# ProPrj_ESP32C3CameraTrigger_2026-09-02_2.net
KiCad netlist of a schematic drawn in EasyEDA Pro
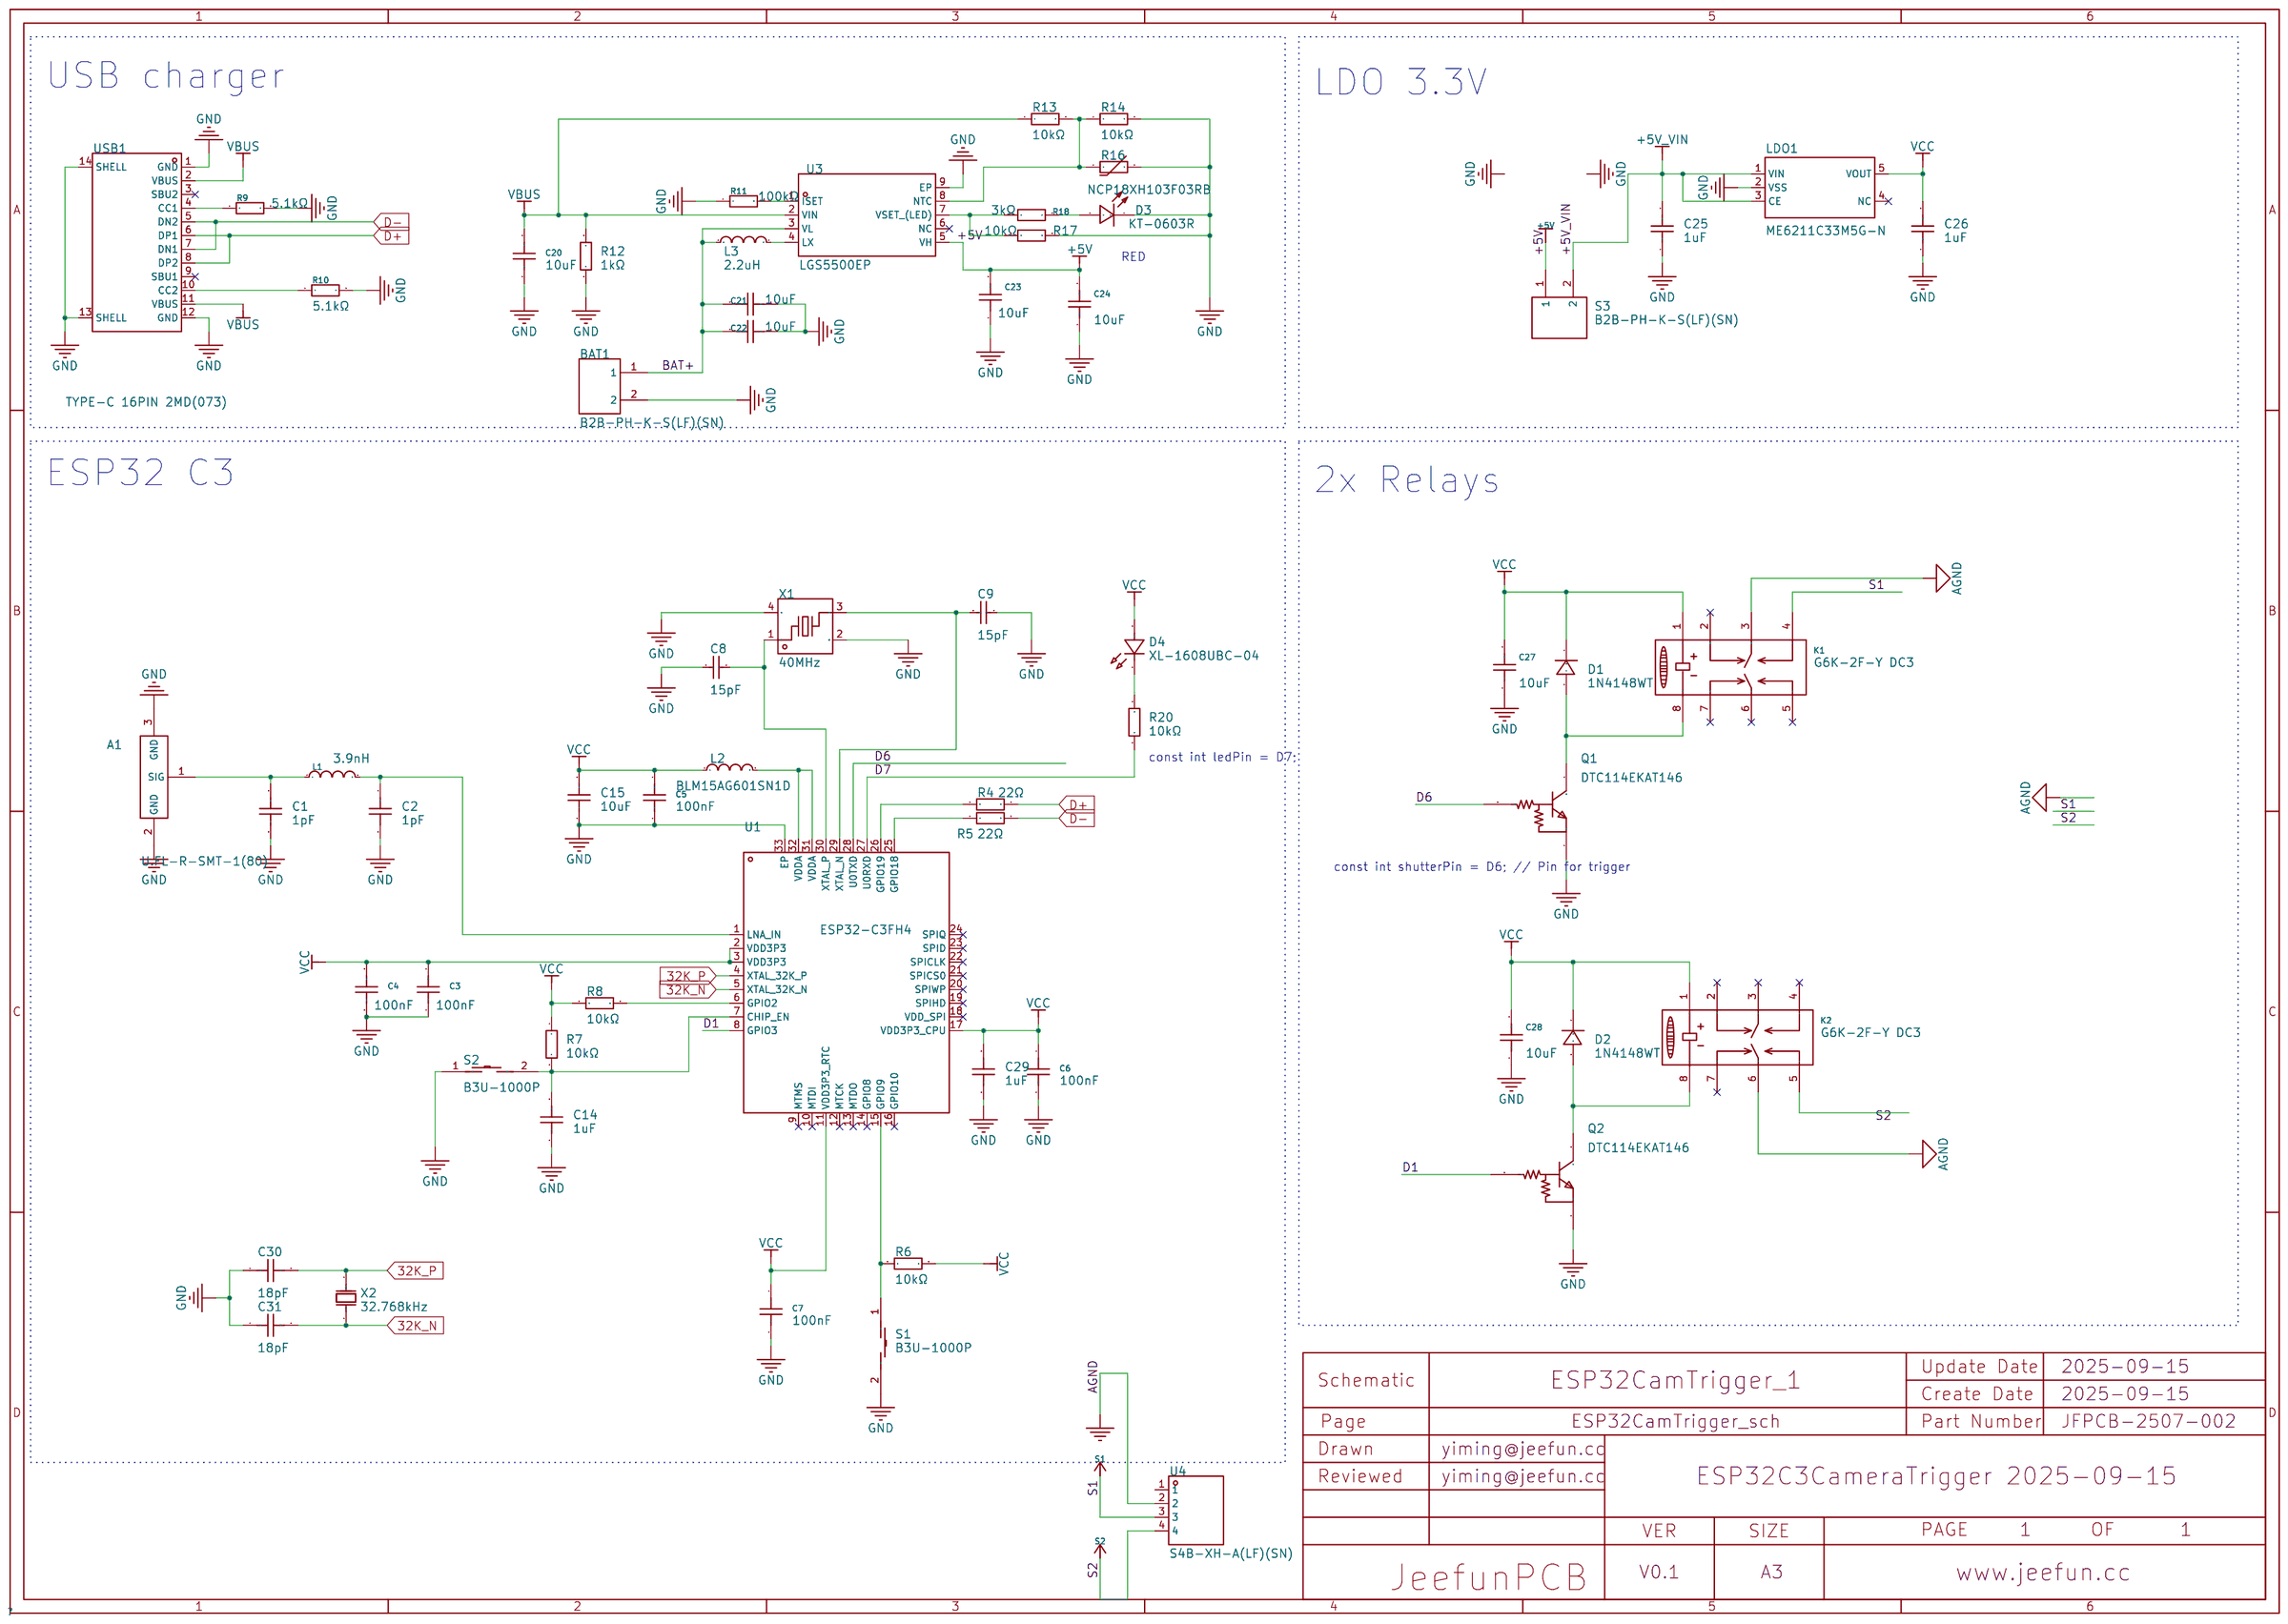
[diagram p0: schematic sheet]

(export (version "E")
  (design (tool "Eeschema 10.0.6"))
  (components
    (comp (ref "A1")
      (value "U.FL-R-SMT-1(80)")
      (footprint "easyedapro:RF-SMD_FRF05002-JSS103M")
      (fields (field (name "Manufacturer") "HRS(广濑)"))
      (libsource (lib "easyedapro") (part "U.FL-R-SMT-1(80)"))
    )
    (comp (ref "BAT1")
      (value "B2B-PH-K-S(LF)(SN)")
      (footprint "easyedapro:CONN-TH_B2B-PH-K-S")
      (fields (field (name "Manufacturer") "JST"))
      (libsource (lib "easyedapro") (part "B2B-PH-K-S(LF)(SN)"))
    )
    (comp (ref "C1")
      (value "1pF")
      (footprint "easyedapro:C0402")
      (fields
        (field (name "Manufacturer Part") "CC0402CRNPO9BN1R0")
        (field (name "Manufacturer") "YAGEO(国巨)")
      )
      (libsource (lib "easyedapro") (part "GCM1555C1H1R0BA16D"))
    )
    (comp (ref "C2")
      (value "1pF")
      (footprint "easyedapro:C0402")
      (fields
        (field (name "Manufacturer Part") "CC0402CRNPO9BN1R0")
        (field (name "Manufacturer") "YAGEO(国巨)")
      )
      (libsource (lib "easyedapro") (part "GCM1555C1H1R0BA16D"))
    )
    (comp (ref "C3")
      (value "100nF")
      (footprint "easyedapro:C0402")
      (fields
        (field (name "Manufacturer Part") "GRM155R71H104KE14D")
        (field (name "Manufacturer") "muRata(村田)")
      )
      (libsource (lib "easyedapro") (part "GRM155R71H104KE14D"))
    )
    (comp (ref "C4")
      (value "100nF")
      (footprint "easyedapro:C0402")
      (fields
        (field (name "Manufacturer Part") "GRM155R71H104KE14D")
        (field (name "Manufacturer") "muRata(村田)")
      )
      (libsource (lib "easyedapro") (part "GRM155R71H104KE14D"))
    )
    (comp (ref "C5")
      (value "100nF")
      (footprint "easyedapro:C0402")
      (fields
        (field (name "Manufacturer Part") "GRM155R71H104KE14D")
        (field (name "Manufacturer") "muRata(村田)")
      )
      (libsource (lib "easyedapro") (part "GRM155R71H104KE14D"))
    )
    (comp (ref "C6")
      (value "100nF")
      (footprint "easyedapro:C0402")
      (fields
        (field (name "Manufacturer Part") "GRM155R71H104KE14D")
        (field (name "Manufacturer") "muRata(村田)")
      )
      (libsource (lib "easyedapro") (part "GRM155R71H104KE14D"))
    )
    (comp (ref "C7")
      (value "100nF")
      (footprint "easyedapro:C0402")
      (fields
        (field (name "Manufacturer Part") "GRM155R71H104KE14D")
        (field (name "Manufacturer") "muRata(村田)")
      )
      (libsource (lib "easyedapro") (part "GRM155R71H104KE14D"))
    )
    (comp (ref "C8")
      (value "15pF")
      (footprint "easyedapro:C0402")
      (fields
        (field (name "Manufacturer Part") "GJM1555C1H150FB01D")
        (field (name "Manufacturer") "muRata(村田)")
      )
      (libsource (lib "easyedapro") (part "GJM1555C1H150FB01D"))
    )
    (comp (ref "C9")
      (value "15pF")
      (footprint "easyedapro:C0402")
      (fields
        (field (name "Manufacturer Part") "GJM1555C1H150FB01D")
        (field (name "Manufacturer") "muRata(村田)")
      )
      (libsource (lib "easyedapro") (part "GJM1555C1H150FB01D"))
    )
    (comp (ref "C14")
      (value "1uF")
      (footprint "easyedapro:C0603")
      (fields
        (field (name "Manufacturer Part") "CGA0603X5R105K500JT")
        (field (name "Manufacturer") "HRE(芯声)")
      )
      (libsource (lib "easyedapro") (part "CGA0603X5R105K500JT"))
    )
    (comp (ref "C15")
      (value "10uF")
      (footprint "easyedapro:C0603")
      (description "Capacitance:10uF Tolerance:±20% Tolerance:±20% Voltage Rating:25V Temperature Coefficient:X5R")
      (fields
        (field (name "Manufacturer Part") "CL10A106MA8NRNC")
        (field (name "Manufacturer") "SAMSUNG(三星)")
      )
      (libsource (lib "easyedapro") (part "CGA0603X5R106K100JT"))
    )
    (comp (ref "C20")
      (value "10uF")
      (footprint "easyedapro:C0603")
      (fields
        (field (name "Manufacturer Part") "CL10A106MA8NRNC")
        (field (name "Manufacturer") "SAMSUNG(三星)")
      )
      (libsource (lib "easyedapro") (part "CL10A106MA8NRNC"))
    )
    (comp (ref "C21")
      (value "10uF")
      (footprint "easyedapro:C0603")
      (fields
        (field (name "Manufacturer Part") "CL10A106MA8NRNC")
        (field (name "Manufacturer") "SAMSUNG(三星)")
      )
      (libsource (lib "easyedapro") (part "CL10A106MA8NRNC"))
    )
    (comp (ref "C22")
      (value "10uF")
      (footprint "easyedapro:C0603")
      (fields
        (field (name "Manufacturer Part") "CL10A106MA8NRNC")
        (field (name "Manufacturer") "SAMSUNG(三星)")
      )
      (libsource (lib "easyedapro") (part "CL10A106MA8NRNC"))
    )
    (comp (ref "C23")
      (value "10uF")
      (footprint "easyedapro:C0603")
      (fields
        (field (name "Manufacturer Part") "CL10A106MA8NRNC")
        (field (name "Manufacturer") "SAMSUNG(三星)")
      )
      (libsource (lib "easyedapro") (part "CL10A106MA8NRNC"))
    )
    (comp (ref "C24")
      (value "10uF")
      (footprint "easyedapro:C0603")
      (fields
        (field (name "Manufacturer Part") "CL10A106MA8NRNC")
        (field (name "Manufacturer") "SAMSUNG(三星)")
      )
      (libsource (lib "easyedapro") (part "CL10A106MA8NRNC"))
    )
    (comp (ref "C25")
      (value "1uF")
      (footprint "easyedapro:C0603")
      (fields
        (field (name "Manufacturer Part") "CGA0603X5R105K500JT")
        (field (name "Manufacturer") "HRE(芯声)")
      )
      (libsource (lib "easyedapro") (part "CGA0603X5R105K500JT"))
    )
    (comp (ref "C26")
      (value "1uF")
      (footprint "easyedapro:C0603")
      (fields
        (field (name "Manufacturer Part") "CGA0603X5R105K500JT")
        (field (name "Manufacturer") "HRE(芯声)")
      )
      (libsource (lib "easyedapro") (part "CGA0603X5R105K500JT"))
    )
    (comp (ref "C27")
      (value "10uF")
      (footprint "easyedapro:C0603")
      (fields
        (field (name "Manufacturer Part") "CL10A106MA8NRNC")
        (field (name "Manufacturer") "SAMSUNG(三星)")
      )
      (libsource (lib "easyedapro") (part "CL10A106MA8NRNC"))
    )
    (comp (ref "C28")
      (value "10uF")
      (footprint "easyedapro:C0603")
      (fields
        (field (name "Manufacturer Part") "CL10A106MA8NRNC")
        (field (name "Manufacturer") "SAMSUNG(三星)")
      )
      (libsource (lib "easyedapro") (part "CL10A106MA8NRNC"))
    )
    (comp (ref "C29")
      (value "1uF")
      (footprint "easyedapro:C0603")
      (fields
        (field (name "Manufacturer Part") "CGA0603X5R105K500JT")
        (field (name "Manufacturer") "HRE(芯声)")
      )
      (libsource (lib "easyedapro") (part "CGA0603X5R105K500JT"))
    )
    (comp (ref "C30")
      (value "18pF")
      (footprint "easyedapro:C0402")
      (fields
        (field (name "Manufacturer Part") "GRM1555C1H180FA01D")
        (field (name "Manufacturer") "muRata(村田)")
      )
      (libsource (lib "easyedapro") (part "GRM1555C1H180FA01D"))
    )
    (comp (ref "C31")
      (value "18pF")
      (footprint "easyedapro:C0402")
      (fields
        (field (name "Manufacturer Part") "GRM1555C1H180FA01D")
        (field (name "Manufacturer") "muRata(村田)")
      )
      (libsource (lib "easyedapro") (part "GRM1555C1H180FA01D"))
    )
    (comp (ref "D1")
      (value "1N4148WT")
      (footprint "easyedapro:SOD-523_L1.2-W0.8-LS1.6-RD")
      (fields (field (name "Manufacturer") "onsemi(安森美)"))
      (libsource (lib "easyedapro") (part "1N4148WT_C232841"))
    )
    (comp (ref "D2")
      (value "1N4148WT")
      (footprint "easyedapro:SOD-523_L1.2-W0.8-LS1.6-RD")
      (fields (field (name "Manufacturer") "onsemi(安森美)"))
      (libsource (lib "easyedapro") (part "1N4148WT_C232841"))
    )
    (comp (ref "D3")
      (value "KT-0603R")
      (footprint "easyedapro:LED0603-RD")
      (fields (field (name "Manufacturer") "KENTO"))
      (libsource (lib "easyedapro") (part "KT-0603R"))
    )
    (comp (ref "D4")
      (value "XL-1608UBC-04")
      (footprint "easyedapro:LED0603-RD_BLUE")
      (fields (field (name "Manufacturer") "XINGLIGHT(成兴光)"))
      (libsource (lib "easyedapro") (part "XL-1608UBC-04"))
    )
    (comp (ref "K1")
      (value "G6K-2F-Y DC3")
      (footprint "easyedapro:RELAY-SMD_G6K-2F-Y")
      (fields (field (name "Manufacturer") "OMRON(欧姆龙)"))
      (libsource (lib "easyedapro") (part "G6K-2F-Y3VDC"))
    )
    (comp (ref "K2")
      (value "G6K-2F-Y DC3")
      (footprint "easyedapro:RELAY-SMD_G6K-2F-Y")
      (fields (field (name "Manufacturer") "OMRON(欧姆龙)"))
      (libsource (lib "easyedapro") (part "G6K-2F-Y3VDC"))
    )
    (comp (ref "L1")
      (value "3.9nH")
      (footprint "easyedapro:L0402")
      (fields (field (name "Manufacturer Part") "LQG15HS3N9S02D") (field (name "Manufacturer") "muRata(村田)"))
      (libsource (lib "easyedapro") (part "LQG15HS3N9S02D"))
    )
    (comp (ref "L2")
      (value "BLM15AG601SN1D")
      (footprint "easyedapro:L0603")
      (fields (field (name "Manufacturer") "muRata(村田)"))
      (libsource (lib "easyedapro") (part "ACMS160808A3012A"))
    )
    (comp (ref "L3")
      (value "2.2uH")
      (footprint "easyedapro:IND-SMD_L7.1-W6.5-P5.60")
      (fields (field (name "Manufacturer Part") "SPM6530T-2R2M") (field (name "Manufacturer") "TDK"))
      (libsource (lib "easyedapro") (part "SPM6530T-2R2M"))
    )
    (comp (ref "LDO1")
      (value "ME6211C33M5G-N")
      (footprint "easyedapro:SOT-23-5_L3.0-W1.7-P0.95-LS2.8-BL")
      (fields (field (name "Manufacturer") "MICRONE(南京微盟)"))
      (libsource (lib "easyedapro") (part "ME6211C33M5G-N"))
    )
    (comp (ref "Q1")
      (value "DTC114EKAT146")
      (footprint "easyedapro:SOT-346_L2.9-W1.6-P1.90-LS2.8-TR-CW")
      (fields (field (name "Manufacturer") "ROHM(罗姆)"))
      (libsource (lib "easyedapro") (part "DTC114EKAT146"))
    )
    (comp (ref "Q2")
      (value "DTC114EKAT146")
      (footprint "easyedapro:SOT-346_L2.9-W1.6-P1.90-LS2.8-TR-CW")
      (fields (field (name "Manufacturer") "ROHM(罗姆)"))
      (libsource (lib "easyedapro") (part "DTC114EKAT146"))
    )
    (comp (ref "R4")
      (value "22Ω")
      (footprint "easyedapro:R0402")
      (fields (field (name "Manufacturer Part") "RC0402JR-0722RL") (field (name "Manufacturer") "YAGEO(国巨)"))
      (libsource (lib "easyedapro") (part "RC0402JR-0722RL"))
    )
    (comp (ref "R5")
      (value "22Ω")
      (footprint "easyedapro:R0402")
      (fields (field (name "Manufacturer Part") "RC0402JR-0722RL") (field (name "Manufacturer") "YAGEO(国巨)"))
      (libsource (lib "easyedapro") (part "RC0402JR-0722RL"))
    )
    (comp (ref "R6")
      (value "10kΩ")
      (footprint "easyedapro:R0402")
      (fields (field (name "Manufacturer Part") "RC0402FR-0710KL") (field (name "Manufacturer") "YAGEO(国巨)"))
      (libsource (lib "easyedapro") (part "RC0402FR-0710KL"))
    )
    (comp (ref "R7")
      (value "10kΩ")
      (footprint "easyedapro:R0402")
      (fields (field (name "Manufacturer Part") "RC0402FR-0710KL") (field (name "Manufacturer") "YAGEO(国巨)"))
      (libsource (lib "easyedapro") (part "RC0402FR-0710KL"))
    )
    (comp (ref "R8")
      (value "10kΩ")
      (footprint "easyedapro:R0402")
      (fields (field (name "Manufacturer Part") "RC0402FR-0710KL") (field (name "Manufacturer") "YAGEO(国巨)"))
      (libsource (lib "easyedapro") (part "RC0402FR-0710KL"))
    )
    (comp (ref "R9")
      (value "5.1kΩ")
      (footprint "easyedapro:R0402")
      (fields
        (field (name "Manufacturer Part") "0402WGF5101TCE")
        (field (name "Manufacturer") "UNI-ROYAL(厚声)")
      )
      (libsource (lib "easyedapro") (part "0402WGF5101TCE"))
    )
    (comp (ref "R10")
      (value "5.1kΩ")
      (footprint "easyedapro:R0402")
      (fields
        (field (name "Manufacturer Part") "0402WGF5101TCE")
        (field (name "Manufacturer") "UNI-ROYAL(厚声)")
      )
      (libsource (lib "easyedapro") (part "0402WGF5101TCE"))
    )
    (comp (ref "R11")
      (value "100kΩ")
      (footprint "easyedapro:R0402")
      (fields
        (field (name "Manufacturer Part") "0402WGF1003TCE")
        (field (name "Manufacturer") "UNI-ROYAL(厚声)")
      )
      (libsource (lib "easyedapro") (part "0402WGF1003TCE"))
    )
    (comp (ref "R12")
      (value "1kΩ")
      (footprint "easyedapro:R0603")
      (fields
        (field (name "Manufacturer Part") "0603WAJ0102T5E")
        (field (name "Manufacturer") "UNI-ROYAL(厚声)")
      )
      (libsource (lib "easyedapro") (part "0603WAJ0102T5E"))
    )
    (comp (ref "R13")
      (value "10kΩ")
      (footprint "easyedapro:R0402")
      (fields (field (name "Manufacturer Part") "RC0402FR-0710KL") (field (name "Manufacturer") "YAGEO(国巨)"))
      (libsource (lib "easyedapro") (part "RC0402FR-0710KL"))
    )
    (comp (ref "R14")
      (value "10kΩ")
      (footprint "easyedapro:R0402")
      (fields (field (name "Manufacturer Part") "RC0402FR-0710KL") (field (name "Manufacturer") "YAGEO(国巨)"))
      (libsource (lib "easyedapro") (part "RC0402FR-0710KL"))
    )
    (comp (ref "R16")
      (value "NCP18XH103F03RB")
      (footprint "easyedapro:R0603")
      (fields (field (name "Manufacturer") "muRata(村田)"))
      (libsource (lib "easyedapro") (part "NCP18XH103F03RB"))
    )
    (comp (ref "R17")
      (value "10kΩ")
      (footprint "easyedapro:R0402")
      (fields (field (name "Manufacturer Part") "RC0402FR-0710KL") (field (name "Manufacturer") "YAGEO(国巨)"))
      (libsource (lib "easyedapro") (part "RC0402FR-0710KL"))
    )
    (comp (ref "R18")
      (value "3kΩ")
      (footprint "easyedapro:R0603")
      (fields
        (field (name "Manufacturer Part") "0402WGF3001TCE")
        (field (name "Manufacturer") "UNI-ROYAL(厚声)")
      )
      (libsource (lib "easyedapro") (part "0603WAF3001T5E"))
    )
    (comp (ref "R20")
      (value "10kΩ")
      (footprint "easyedapro:R0402")
      (fields (field (name "Manufacturer Part") "RC0402FR-0710KL") (field (name "Manufacturer") "YAGEO(国巨)"))
      (libsource (lib "easyedapro") (part "RC0402FR-0710KL"))
    )
    (comp (ref "S1")
      (value "B3U-1000P")
      (footprint "easyedapro:KEY-SMD_B3U-1000PM")
      (fields (field (name "Manufacturer") "OMRON(欧姆龙)"))
      (libsource (lib "easyedapro") (part "B3U-1000P"))
    )
    (comp (ref "S2")
      (value "B3U-1000P")
      (footprint "easyedapro:KEY-SMD_B3U-1000PM")
      (fields (field (name "Manufacturer") "OMRON(欧姆龙)"))
      (libsource (lib "easyedapro") (part "B3U-1000P"))
    )
    (comp (ref "S3")
      (value "B2B-PH-K-S(LF)(SN)")
      (footprint "easyedapro:CONN-TH_B2B-PH-K-S")
      (fields (field (name "Manufacturer") "JST"))
      (libsource (lib "easyedapro") (part "B2B-PH-K-S(LF)(SN)"))
    )
    (comp (ref "U1")
      (value "ESP32-C3FH4")
      (footprint "easyedapro:QFN-32_L5.0-W5.0-P0.50-TL-EP3.7")
      (fields (field (name "Manufacturer") "ESPRESSIF(乐鑫)"))
      (libsource (lib "easyedapro") (part "ESP32-C3"))
    )
    (comp (ref "U3")
      (value "LGS5500EP")
      (footprint "easyedapro:ESOP-8_L4.9-W3.9-P1.27-LS6.0-TL-EP3.3")
      (fields (field (name "Manufacturer") "Legend-Si(棱晶半导体)"))
      (libsource (lib "easyedapro") (part "LGS5500EP"))
    )
    (comp (ref "U4")
      (value "S4B-XH-A(LF)(SN)")
      (footprint "easyedapro:CONN-TH_S4B-XH-A-LF-SN")
      (fields (field (name "Manufacturer") "JST"))
      (libsource (lib "easyedapro") (part "S4B-XH-A (LF)(SN)"))
    )
    (comp (ref "USB1")
      (value "TYPE-C 16PIN 2MD(073)")
      (footprint "easyedapro:USB-C-SMD_TYPE-C-6PIN-2MD-073")
      (fields (field (name "Manufacturer") "SHOU HAN(首韩)"))
      (libsource (lib "easyedapro") (part "TYPE-C 16PIN 2MD(073)"))
    )
    (comp (ref "X1")
      (value "40MHz")
      (footprint "easyedapro:CRYSTAL-SMD_4P-L2.0-W1.6-BL-2")
      (fields (field (name "Manufacturer Part") "T201640MFBDE2X") (field (name "Manufacturer") "YJX(雅晶鑫)"))
      (libsource (lib "easyedapro") (part "T201640MFBDE2X"))
    )
    (comp (ref "X2")
      (value "32.768kHz")
      (footprint "easyedapro:CRYSTAL-SMD_L3.2-W1.5-1")
      (fields
        (field (name "Manufacturer Part") "XKXGI-SUA-32.768K")
        (field (name "Manufacturer") "YXC(扬兴晶振)")
      )
      (libsource (lib "easyedapro") (part "XKXGI-SUA-32.768K"))
    )
  )
  (nets
    (net (code "1") (name "+5V") (class "Default")
      (node (ref "C23") (pin "2") (pinfunction "2_2") (pintype "input"))
      (node (ref "C24") (pin "2") (pinfunction "2_2") (pintype "input"))
      (node (ref "S3") (pin "1") (pinfunction "1_1") (pintype "input"))
      (node (ref "U3") (pin "5") (pinfunction "VH_5") (pintype "unspecified"))
    )
    (net (code "2") (name "+5V_VIN") (class "Default")
      (node (ref "C25") (pin "2") (pinfunction "2_2") (pintype "unspecified"))
      (node (ref "LDO1") (pin "1") (pinfunction "VIN_1") (pintype "unspecified"))
      (node (ref "LDO1") (pin "3") (pinfunction "CE_3") (pintype "unspecified"))
      (node (ref "S3") (pin "2") (pinfunction "2_2") (pintype "input"))
    )
    (net (code "3") (name "/BAT+") (class "Default")
      (node (ref "BAT1") (pin "1") (pinfunction "1_1") (pintype "input"))
      (node (ref "C21") (pin "2") (pinfunction "2_2") (pintype "input"))
      (node (ref "C22") (pin "2") (pinfunction "2_2") (pintype "input"))
      (node (ref "L3") (pin "1") (pinfunction "1_1") (pintype "unspecified"))
      (node (ref "U3") (pin "3") (pinfunction "VL_3") (pintype "unspecified"))
    )
    (net (code "4") (name "/D1") (class "Default")
      (node (ref "Q2") (pin "2") (pinfunction "B_2") (pintype "unspecified"))
      (node (ref "U1") (pin "8") (pinfunction "GPIO3_8") (pintype "unspecified"))
    )
    (net (code "5") (name "/D6") (class "Default")
      (node (ref "Q1") (pin "2") (pinfunction "B_2") (pintype "unspecified"))
      (node (ref "U1") (pin "28") (pinfunction "U0TXD_28") (pintype "unspecified"))
    )
    (net (code "6") (name "/D7") (class "Default")
      (node (ref "R20") (pin "1") (pinfunction "1_1") (pintype "input"))
      (node (ref "U1") (pin "27") (pinfunction "U0RXD_27") (pintype "unspecified"))
    )
    (net (code "7") (name "32K_N") (class "Default")
      (node (ref "C31") (pin "2") (pinfunction "2_2") (pintype "unspecified"))
      (node (ref "U1") (pin "5") (pinfunction "XTAL_32K_N_5") (pintype "unspecified"))
      (node (ref "X2") (pin "1") (pinfunction "OSC1_1") (pintype "input"))
    )
    (net (code "8") (name "32K_P") (class "Default")
      (node (ref "C30") (pin "2") (pinfunction "2_2") (pintype "unspecified"))
      (node (ref "U1") (pin "4") (pinfunction "XTAL_32K_P_4") (pintype "unspecified"))
      (node (ref "X2") (pin "2") (pinfunction "OSC2_2") (pintype "input"))
    )
    (net (code "9") (name "AGND") (class "Default")
      (node (ref "K1") (pin "3") (pinfunction "3_3") (pintype "input"))
      (node (ref "K2") (pin "6") (pinfunction "6_6") (pintype "input"))
      (node (ref "U4") (pin "2") (pinfunction "2_2") (pintype "unspecified"))
    )
    (net (code "10") (name "D+") (class "Default")
      (node (ref "R4") (pin "2") (pinfunction "2_2") (pintype "input"))
      (node (ref "USB1") (pin "6") (pinfunction "DP1_6") (pintype "unspecified"))
      (node (ref "USB1") (pin "8") (pinfunction "DP2_8") (pintype "unspecified"))
    )
    (net (code "11") (name "D-") (class "Default")
      (node (ref "R5") (pin "2") (pinfunction "2_2") (pintype "input"))
      (node (ref "USB1") (pin "5") (pinfunction "DN2_5") (pintype "unspecified"))
      (node (ref "USB1") (pin "7") (pinfunction "DN1_7") (pintype "unspecified"))
    )
    (net (code "12") (name "GND") (class "Default")
      (node (ref "A1") (pin "2") (pinfunction "GND_2") (pintype "unspecified"))
      (node (ref "A1") (pin "3") (pinfunction "GND_3") (pintype "unspecified"))
      (node (ref "BAT1") (pin "2") (pinfunction "2_2") (pintype "input"))
      (node (ref "C1") (pin "2") (pinfunction "2_2") (pintype "unspecified"))
      (node (ref "C14") (pin "1") (pinfunction "1_1") (pintype "unspecified"))
      (node (ref "C15") (pin "1") (pinfunction "1_1") (pintype "unspecified"))
      (node (ref "C2") (pin "2") (pinfunction "2_2") (pintype "unspecified"))
      (node (ref "C20") (pin "1") (pinfunction "1_1") (pintype "input"))
      (node (ref "C21") (pin "1") (pinfunction "1_1") (pintype "input"))
      (node (ref "C22") (pin "1") (pinfunction "1_1") (pintype "input"))
      (node (ref "C23") (pin "1") (pinfunction "1_1") (pintype "input"))
      (node (ref "C24") (pin "1") (pinfunction "1_1") (pintype "input"))
      (node (ref "C25") (pin "1") (pinfunction "1_1") (pintype "unspecified"))
      (node (ref "C26") (pin "1") (pinfunction "1_1") (pintype "unspecified"))
      (node (ref "C27") (pin "1") (pinfunction "1_1") (pintype "input"))
      (node (ref "C28") (pin "1") (pinfunction "1_1") (pintype "input"))
      (node (ref "C29") (pin "1") (pinfunction "1_1") (pintype "unspecified"))
      (node (ref "C3") (pin "1") (pinfunction "1_1") (pintype "input"))
      (node (ref "C30") (pin "1") (pinfunction "1_1") (pintype "unspecified"))
      (node (ref "C31") (pin "1") (pinfunction "1_1") (pintype "unspecified"))
      (node (ref "C4") (pin "1") (pinfunction "1_1") (pintype "input"))
      (node (ref "C5") (pin "2") (pinfunction "2_2") (pintype "input"))
      (node (ref "C6") (pin "2") (pinfunction "2_2") (pintype "input"))
      (node (ref "C7") (pin "2") (pinfunction "2_2") (pintype "input"))
      (node (ref "C8") (pin "1") (pinfunction "1_1") (pintype "input"))
      (node (ref "C9") (pin "2") (pinfunction "2_2") (pintype "input"))
      (node (ref "D3") (pin "1") (pinfunction "K_1") (pintype "unspecified"))
      (node (ref "LDO1") (pin "2") (pinfunction "VSS_2") (pintype "unspecified"))
      (node (ref "Q1") (pin "1") (pinfunction "E_1") (pintype "unspecified"))
      (node (ref "Q2") (pin "1") (pinfunction "E_1") (pintype "unspecified"))
      (node (ref "R10") (pin "2") (pinfunction "2_2") (pintype "input"))
      (node (ref "R11") (pin "1") (pinfunction "1_1") (pintype "input"))
      (node (ref "R12") (pin "1") (pinfunction "1_1") (pintype "input"))
      (node (ref "R14") (pin "2") (pinfunction "2_2") (pintype "input"))
      (node (ref "R16") (pin "2") (pinfunction "2_2") (pintype "input"))
      (node (ref "R17") (pin "2") (pinfunction "2_2") (pintype "input"))
      (node (ref "R9") (pin "2") (pinfunction "2_2") (pintype "input"))
      (node (ref "S1") (pin "2") (pinfunction "2_2") (pintype "unspecified"))
      (node (ref "S2") (pin "1") (pinfunction "1_1") (pintype "unspecified"))
      (node (ref "U1") (pin "33") (pinfunction "EP_33") (pintype "unspecified"))
      (node (ref "U3") (pin "9") (pinfunction "EP_9") (pintype "unspecified"))
      (node (ref "USB1") (pin "1") (pinfunction "GND_1") (pintype "unspecified"))
      (node (ref "USB1") (pin "12") (pinfunction "GND_12") (pintype "unspecified"))
      (node (ref "USB1") (pin "13") (pinfunction "SHELL_13") (pintype "unspecified"))
      (node (ref "USB1") (pin "14") (pinfunction "SHELL_14") (pintype "unspecified"))
      (node (ref "X1") (pin "2") (pinfunction "GND_2") (pintype "input"))
      (node (ref "X1") (pin "4") (pinfunction "GND_4") (pintype "input"))
    )
    (net (code "13") (name "Net-(A1-SIG)") (class "Default")
      (node (ref "A1") (pin "1") (pinfunction "SIG_1") (pintype "unspecified"))
      (node (ref "C1") (pin "1") (pinfunction "1_1") (pintype "unspecified"))
      (node (ref "L1") (pin "1") (pinfunction "1_1") (pintype "input"))
    )
    (net (code "14") (name "Net-(D1-A)") (class "Default")
      (node (ref "D1") (pin "2") (pinfunction "A_2") (pintype "unspecified"))
      (node (ref "K1") (pin "8") (pinfunction "8_8") (pintype "input"))
      (node (ref "Q1") (pin "3") (pinfunction "C_3") (pintype "unspecified"))
    )
    (net (code "15") (name "Net-(D2-A)") (class "Default")
      (node (ref "D2") (pin "2") (pinfunction "A_2") (pintype "unspecified"))
      (node (ref "K2") (pin "8") (pinfunction "8_8") (pintype "input"))
      (node (ref "Q2") (pin "3") (pinfunction "C_3") (pintype "unspecified"))
    )
    (net (code "16") (name "Net-(D3-A)") (class "Default")
      (node (ref "D3") (pin "2") (pinfunction "A_2") (pintype "unspecified"))
      (node (ref "R18") (pin "2") (pinfunction "2_2") (pintype "input"))
    )
    (net (code "17") (name "Net-(D4-K)") (class "Default")
      (node (ref "D4") (pin "1") (pinfunction "K_1") (pintype "unspecified"))
      (node (ref "R20") (pin "2") (pinfunction "2_2") (pintype "input"))
    )
    (net (code "18") (name "Net-(L2-Pad2)") (class "Default")
      (node (ref "L2") (pin "2") (pinfunction "2_2") (pintype "unspecified"))
      (node (ref "U1") (pin "31") (pinfunction "VDDA_31") (pintype "unspecified"))
      (node (ref "U1") (pin "32") (pinfunction "VDDA_32") (pintype "unspecified"))
    )
    (net (code "19") (name "Net-(U1-CHIP_EN)") (class "Default")
      (node (ref "C14") (pin "2") (pinfunction "2_2") (pintype "unspecified"))
      (node (ref "R7") (pin "2") (pinfunction "2_2") (pintype "input"))
      (node (ref "S2") (pin "2") (pinfunction "2_2") (pintype "unspecified"))
      (node (ref "U1") (pin "7") (pinfunction "CHIP_EN_7") (pintype "unspecified"))
    )
    (net (code "20") (name "Net-(U1-GPIO2)") (class "Default")
      (node (ref "R8") (pin "2") (pinfunction "2_2") (pintype "input"))
      (node (ref "U1") (pin "6") (pinfunction "GPIO2_6") (pintype "unspecified"))
    )
    (net (code "21") (name "Net-(U1-GPIO9)") (class "Default")
      (node (ref "R6") (pin "1") (pinfunction "1_1") (pintype "input"))
      (node (ref "S1") (pin "1") (pinfunction "1_1") (pintype "unspecified"))
      (node (ref "U1") (pin "15") (pinfunction "GPIO9_15") (pintype "unspecified"))
    )
    (net (code "22") (name "Net-(U1-GPIO18)") (class "Default")
      (node (ref "R5") (pin "1") (pinfunction "1_1") (pintype "input"))
      (node (ref "U1") (pin "25") (pinfunction "GPIO18_25") (pintype "unspecified"))
    )
    (net (code "23") (name "Net-(U1-GPIO19)") (class "Default")
      (node (ref "R4") (pin "1") (pinfunction "1_1") (pintype "input"))
      (node (ref "U1") (pin "26") (pinfunction "GPIO19_26") (pintype "unspecified"))
    )
    (net (code "24") (name "Net-(U1-LNA_IN)") (class "Default")
      (node (ref "C2") (pin "1") (pinfunction "1_1") (pintype "unspecified"))
      (node (ref "L1") (pin "2") (pinfunction "2_2") (pintype "input"))
      (node (ref "U1") (pin "1") (pinfunction "LNA_IN_1") (pintype "unspecified"))
    )
    (net (code "25") (name "Net-(U1-XTAL_N)") (class "Default")
      (node (ref "C9") (pin "1") (pinfunction "1_1") (pintype "input"))
      (node (ref "U1") (pin "29") (pinfunction "XTAL_N_29") (pintype "unspecified"))
      (node (ref "X1") (pin "3") (pinfunction "3_3") (pintype "input"))
    )
    (net (code "26") (name "Net-(U1-XTAL_P)") (class "Default")
      (node (ref "C8") (pin "2") (pinfunction "2_2") (pintype "input"))
      (node (ref "U1") (pin "30") (pinfunction "XTAL_P_30") (pintype "unspecified"))
      (node (ref "X1") (pin "1") (pinfunction "1_1") (pintype "input"))
    )
    (net (code "27") (name "Net-(U3-ISET)") (class "Default")
      (node (ref "R11") (pin "2") (pinfunction "2_2") (pintype "input"))
      (node (ref "U3") (pin "1") (pinfunction "ISET_1") (pintype "unspecified"))
    )
    (net (code "28") (name "Net-(U3-LX)") (class "Default")
      (node (ref "L3") (pin "2") (pinfunction "2_2") (pintype "unspecified"))
      (node (ref "U3") (pin "4") (pinfunction "LX_4") (pintype "unspecified"))
    )
    (net (code "29") (name "Net-(U3-NTC)") (class "Default")
      (node (ref "R13") (pin "2") (pinfunction "2_2") (pintype "input"))
      (node (ref "R14") (pin "1") (pinfunction "1_1") (pintype "input"))
      (node (ref "R16") (pin "1") (pinfunction "1_1") (pintype "input"))
      (node (ref "U3") (pin "8") (pinfunction "NTC_8") (pintype "unspecified"))
    )
    (net (code "30") (name "Net-(U3-VSET_(LED))") (class "Default")
      (node (ref "R17") (pin "1") (pinfunction "1_1") (pintype "input"))
      (node (ref "R18") (pin "1") (pinfunction "1_1") (pintype "input"))
      (node (ref "U3") (pin "7") (pinfunction "VSET_(LED)_7") (pintype "unspecified"))
    )
    (net (code "31") (name "Net-(USB1-CC1)") (class "Default")
      (node (ref "R9") (pin "1") (pinfunction "1_1") (pintype "input"))
      (node (ref "USB1") (pin "4") (pinfunction "CC1_4") (pintype "unspecified"))
    )
    (net (code "32") (name "Net-(USB1-CC2)") (class "Default")
      (node (ref "R10") (pin "1") (pinfunction "1_1") (pintype "input"))
      (node (ref "USB1") (pin "10") (pinfunction "CC2_10") (pintype "unspecified"))
    )
    (net (code "33") (name "S1") (class "Default")
      (node (ref "K1") (pin "4") (pinfunction "4_4") (pintype "input"))
      (node (ref "U4") (pin "3") (pinfunction "3_3") (pintype "unspecified"))
    )
    (net (code "34") (name "S2") (class "Default")
      (node (ref "K2") (pin "5") (pinfunction "5_5") (pintype "input"))
      (node (ref "U4") (pin "4") (pinfunction "4_4") (pintype "unspecified"))
    )
    (net (code "35") (name "VBUS") (class "Default")
      (node (ref "C20") (pin "2") (pinfunction "2_2") (pintype "input"))
      (node (ref "R12") (pin "2") (pinfunction "2_2") (pintype "input"))
      (node (ref "R13") (pin "1") (pinfunction "1_1") (pintype "input"))
      (node (ref "U3") (pin "2") (pinfunction "VIN_2") (pintype "unspecified"))
      (node (ref "USB1") (pin "11") (pinfunction "VBUS_11") (pintype "unspecified"))
      (node (ref "USB1") (pin "2") (pinfunction "VBUS_2") (pintype "unspecified"))
    )
    (net (code "36") (name "VCC") (class "Default")
      (node (ref "C15") (pin "2") (pinfunction "2_2") (pintype "unspecified"))
      (node (ref "C26") (pin "2") (pinfunction "2_2") (pintype "unspecified"))
      (node (ref "C27") (pin "2") (pinfunction "2_2") (pintype "input"))
      (node (ref "C28") (pin "2") (pinfunction "2_2") (pintype "input"))
      (node (ref "C29") (pin "2") (pinfunction "2_2") (pintype "unspecified"))
      (node (ref "C3") (pin "2") (pinfunction "2_2") (pintype "input"))
      (node (ref "C4") (pin "2") (pinfunction "2_2") (pintype "input"))
      (node (ref "C5") (pin "1") (pinfunction "1_1") (pintype "input"))
      (node (ref "C6") (pin "1") (pinfunction "1_1") (pintype "input"))
      (node (ref "C7") (pin "1") (pinfunction "1_1") (pintype "input"))
      (node (ref "D1") (pin "1") (pinfunction "C_1") (pintype "unspecified"))
      (node (ref "D2") (pin "1") (pinfunction "C_1") (pintype "unspecified"))
      (node (ref "D4") (pin "2") (pinfunction "A_2") (pintype "unspecified"))
      (node (ref "K1") (pin "1") (pinfunction "1_1") (pintype "input"))
      (node (ref "K2") (pin "1") (pinfunction "1_1") (pintype "input"))
      (node (ref "L2") (pin "1") (pinfunction "1_1") (pintype "unspecified"))
      (node (ref "LDO1") (pin "5") (pinfunction "VOUT_5") (pintype "unspecified"))
      (node (ref "R6") (pin "2") (pinfunction "2_2") (pintype "input"))
      (node (ref "R7") (pin "1") (pinfunction "1_1") (pintype "input"))
      (node (ref "R8") (pin "1") (pinfunction "1_1") (pintype "input"))
      (node (ref "U1") (pin "11") (pinfunction "VDD3P3_RTC_11") (pintype "unspecified"))
      (node (ref "U1") (pin "17") (pinfunction "VDD3P3_CPU_17") (pintype "unspecified"))
      (node (ref "U1") (pin "2") (pinfunction "VDD3P3_2") (pintype "unspecified"))
      (node (ref "U1") (pin "3") (pinfunction "VDD3P3_3") (pintype "unspecified"))
    )
    (net (code "37") (name "unconnected-(K1-Pad2)") (class "Default")
      (node (ref "K1") (pin "2") (pinfunction "2_2") (pintype "input+no_connect"))
    )
    (net (code "38") (name "unconnected-(K1-Pad5)") (class "Default")
      (node (ref "K1") (pin "5") (pinfunction "5_5") (pintype "input+no_connect"))
    )
    (net (code "39") (name "unconnected-(K1-Pad6)") (class "Default")
      (node (ref "K1") (pin "6") (pinfunction "6_6") (pintype "input+no_connect"))
    )
    (net (code "40") (name "unconnected-(K1-Pad7)") (class "Default")
      (node (ref "K1") (pin "7") (pinfunction "7_7") (pintype "input+no_connect"))
    )
    (net (code "41") (name "unconnected-(K2-Pad2)") (class "Default")
      (node (ref "K2") (pin "2") (pinfunction "2_2") (pintype "input+no_connect"))
    )
    (net (code "42") (name "unconnected-(K2-Pad3)") (class "Default")
      (node (ref "K2") (pin "3") (pinfunction "3_3") (pintype "input+no_connect"))
    )
    (net (code "43") (name "unconnected-(K2-Pad4)") (class "Default")
      (node (ref "K2") (pin "4") (pinfunction "4_4") (pintype "input+no_connect"))
    )
    (net (code "44") (name "unconnected-(K2-Pad7)") (class "Default")
      (node (ref "K2") (pin "7") (pinfunction "7_7") (pintype "input+no_connect"))
    )
    (net (code "45") (name "unconnected-(LDO1-NC-Pad4)") (class "Default")
      (node (ref "LDO1") (pin "4") (pinfunction "NC_4") (pintype "unspecified+no_connect"))
    )
    (net (code "46") (name "unconnected-(U1-GPIO8-Pad14)") (class "Default")
      (node (ref "U1") (pin "14") (pinfunction "GPIO8_14") (pintype "unspecified+no_connect"))
    )
    (net (code "47") (name "unconnected-(U1-GPIO10-Pad16)") (class "Default")
      (node (ref "U1") (pin "16") (pinfunction "GPIO10_16") (pintype "unspecified+no_connect"))
    )
    (net (code "48") (name "unconnected-(U1-MTCK-Pad12)") (class "Default")
      (node (ref "U1") (pin "12") (pinfunction "MTCK_12") (pintype "unspecified+no_connect"))
    )
    (net (code "49") (name "unconnected-(U1-MTDI-Pad10)") (class "Default")
      (node (ref "U1") (pin "10") (pinfunction "MTDI_10") (pintype "unspecified+no_connect"))
    )
    (net (code "50") (name "unconnected-(U1-MTDO-Pad13)") (class "Default")
      (node (ref "U1") (pin "13") (pinfunction "MTDO_13") (pintype "unspecified+no_connect"))
    )
    (net (code "51") (name "unconnected-(U1-MTMS-Pad9)") (class "Default")
      (node (ref "U1") (pin "9") (pinfunction "MTMS_9") (pintype "unspecified+no_connect"))
    )
    (net (code "52") (name "unconnected-(U1-SPICLK-Pad22)") (class "Default")
      (node (ref "U1") (pin "22") (pinfunction "SPICLK_22") (pintype "unspecified+no_connect"))
    )
    (net (code "53") (name "unconnected-(U1-SPICS0-Pad21)") (class "Default")
      (node (ref "U1") (pin "21") (pinfunction "SPICS0_21") (pintype "unspecified+no_connect"))
    )
    (net (code "54") (name "unconnected-(U1-SPID-Pad23)") (class "Default")
      (node (ref "U1") (pin "23") (pinfunction "SPID_23") (pintype "unspecified+no_connect"))
    )
    (net (code "55") (name "unconnected-(U1-SPIHD-Pad19)") (class "Default")
      (node (ref "U1") (pin "19") (pinfunction "SPIHD_19") (pintype "unspecified+no_connect"))
    )
    (net (code "56") (name "unconnected-(U1-SPIQ-Pad24)") (class "Default")
      (node (ref "U1") (pin "24") (pinfunction "SPIQ_24") (pintype "unspecified+no_connect"))
    )
    (net (code "57") (name "unconnected-(U1-SPIWP-Pad20)") (class "Default")
      (node (ref "U1") (pin "20") (pinfunction "SPIWP_20") (pintype "unspecified+no_connect"))
    )
    (net (code "58") (name "unconnected-(U1-VDD_SPI-Pad18)") (class "Default")
      (node (ref "U1") (pin "18") (pinfunction "VDD_SPI_18") (pintype "unspecified+no_connect"))
    )
    (net (code "59") (name "unconnected-(U3-NC-Pad6)") (class "Default")
      (node (ref "U3") (pin "6") (pinfunction "NC_6") (pintype "unspecified+no_connect"))
    )
    (net (code "60") (name "unconnected-(U4-Pad1)") (class "Default")
      (node (ref "U4") (pin "1") (pinfunction "1_1") (pintype "unspecified"))
    )
    (net (code "61") (name "unconnected-(USB1-SBU1-Pad9)") (class "Default")
      (node (ref "USB1") (pin "9") (pinfunction "SBU1_9") (pintype "unspecified+no_connect"))
    )
    (net (code "62") (name "unconnected-(USB1-SBU2-Pad3)") (class "Default")
      (node (ref "USB1") (pin "3") (pinfunction "SBU2_3") (pintype "unspecified+no_connect"))
    )
  )
)
